# top.net
KiCad netlist of a schematic drawn in Altium Designer
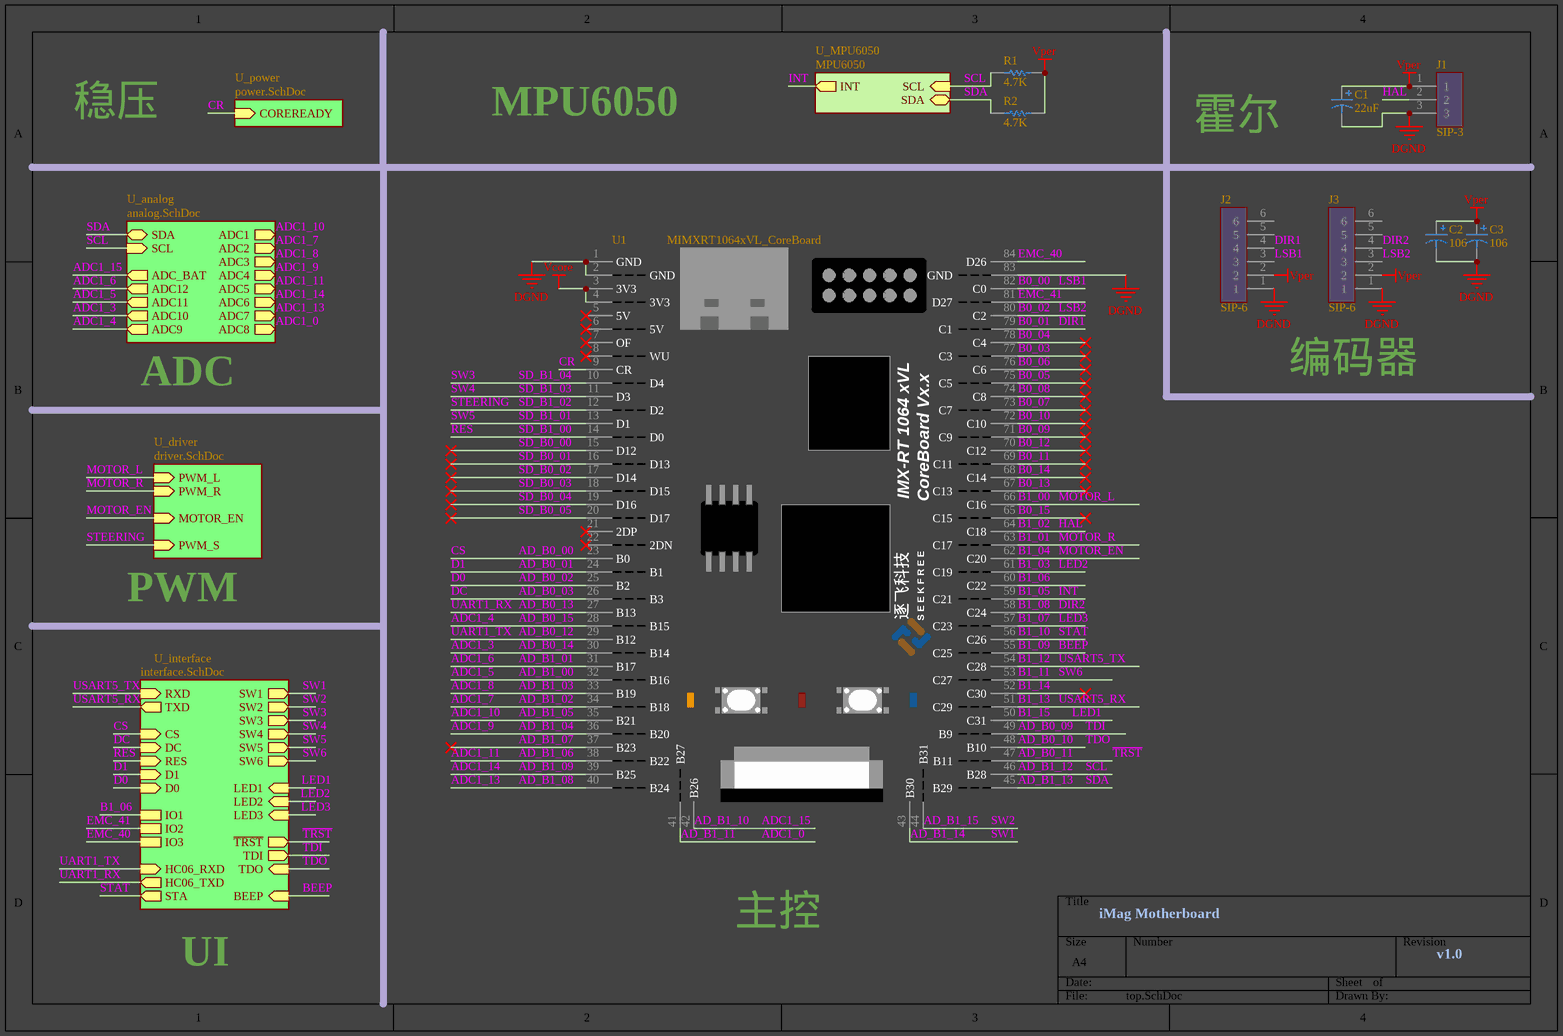
[diagram p0: top.SchDoc]

(export (version "E")
  (design (tool "Eeschema 10.0.6"))
  (components
    (comp (ref "C1")
      (value "22uF")
      (footprint "贴片电解 4*5.4")
      (description "Polarized Capacitor (Axial)")
      (fields (field (name "PUBLISHER") "Altium Limited"))
      (libsource (lib "iMag") (part "电解电容"))
    )
    (comp (ref "C2")
      (value "106")
      (footprint "3216-ce")
      (description "Polarized Capacitor (Axial)")
      (fields (field (name "PUBLISHER") "Altium Limited"))
      (libsource (lib "iMag") (part "电解电容"))
    )
    (comp (ref "C3")
      (value "106")
      (footprint "3216-ce")
      (description "Polarized Capacitor (Axial)")
      (fields (field (name "PUBLISHER") "Altium Limited"))
      (libsource (lib "iMag") (part "电解电容"))
    )
    (comp (ref "J1") (value "SIP-3") (footprint "XH2.54-3SMD") (libsource (lib "iMag") (part "SIP-3")))
    (comp (ref "J2") (value "SIP-6") (footprint "2.54简易牛角座6P") (libsource (lib "iMag") (part "SIP-6")))
    (comp (ref "J3") (value "SIP-6") (footprint "2.54简易牛角座6P") (libsource (lib "iMag") (part "SIP-6")))
    (comp (ref "R1")
      (value "4.7K")
      (footprint "R0402")
      (description "Resistor")
      (fields (field (name "PUBLISHER") "Altium Limited"))
      (libsource (lib "iMag") (part "电阻"))
    )
    (comp (ref "R2")
      (value "4.7K")
      (footprint "R0402")
      (description "Resistor")
      (fields (field (name "PUBLISHER") "Altium Limited"))
      (libsource (lib "iMag") (part "电阻"))
    )
    (comp (ref "U1")
      (value "MIMXRT1064xVL_CoreBoard")
      (footprint "MIMXRT1064xVL_CoreBoard")
      (description "逐飞科技i.MX RT1064核心板整体原理，可直接使用")
      (libsource (lib "iMag") (part "MIMXRT1064xVL_CoreBoard"))
    )
  )
  (nets
    (net (code "1") (name "/ADC1_0") (class "Default")
      (node (ref "U1") (pin "41") (pinfunction "B27_41") (pintype "passive"))
    )
    (net (code "2") (name "/ADC1_3") (class "Default")
      (node (ref "U1") (pin "30") (pinfunction "B14_30") (pintype "passive"))
    )
    (net (code "3") (name "/ADC1_4") (class "Default")
      (node (ref "U1") (pin "28") (pinfunction "B15_28") (pintype "passive"))
    )
    (net (code "4") (name "/ADC1_5") (class "Default")
      (node (ref "U1") (pin "32") (pinfunction "B16_32") (pintype "passive"))
    )
    (net (code "5") (name "/ADC1_6") (class "Default")
      (node (ref "U1") (pin "31") (pinfunction "B17_31") (pintype "passive"))
    )
    (net (code "6") (name "/ADC1_7") (class "Default")
      (node (ref "U1") (pin "34") (pinfunction "B18_34") (pintype "passive"))
    )
    (net (code "7") (name "/ADC1_8") (class "Default")
      (node (ref "U1") (pin "33") (pinfunction "B19_33") (pintype "passive"))
    )
    (net (code "8") (name "/ADC1_9") (class "Default")
      (node (ref "U1") (pin "36") (pinfunction "B20_36") (pintype "passive"))
    )
    (net (code "9") (name "/ADC1_10") (class "Default")
      (node (ref "U1") (pin "35") (pinfunction "B21_35") (pintype "passive"))
    )
    (net (code "10") (name "/ADC1_11") (class "Default")
      (node (ref "U1") (pin "38") (pinfunction "B22_38") (pintype "passive"))
    )
    (net (code "11") (name "/ADC1_13") (class "Default")
      (node (ref "U1") (pin "40") (pinfunction "B24_40") (pintype "passive"))
    )
    (net (code "12") (name "/ADC1_14") (class "Default")
      (node (ref "U1") (pin "39") (pinfunction "B25_39") (pintype "passive"))
    )
    (net (code "13") (name "/ADC1_15") (class "Default")
      (node (ref "U1") (pin "42") (pinfunction "B26_42") (pintype "passive"))
    )
    (net (code "14") (name "/AD_B0_00") (class "Default")
      (node (ref "U1") (pin "23") (pinfunction "B0_23") (pintype "passive"))
    )
    (net (code "15") (name "/AD_B0_01") (class "Default")
      (node (ref "U1") (pin "24") (pinfunction "B1_24") (pintype "passive"))
    )
    (net (code "16") (name "/AD_B0_02") (class "Default")
      (node (ref "U1") (pin "25") (pinfunction "B2_25") (pintype "passive"))
    )
    (net (code "17") (name "/AD_B0_03") (class "Default")
      (node (ref "U1") (pin "26") (pinfunction "B3_26") (pintype "passive"))
    )
    (net (code "18") (name "/AD_B0_09") (class "Default")
      (node (ref "U1") (pin "49") (pinfunction "B9_49") (pintype "passive"))
    )
    (net (code "19") (name "/AD_B0_10") (class "Default")
      (node (ref "U1") (pin "48") (pinfunction "B10_48") (pintype "passive"))
    )
    (net (code "20") (name "/AD_B0_11") (class "Default")
      (node (ref "U1") (pin "47") (pinfunction "B11_47") (pintype "passive"))
    )
    (net (code "21") (name "/AD_B0_12") (class "Default")
      (node (ref "U1") (pin "29") (pinfunction "B12_29") (pintype "passive"))
    )
    (net (code "22") (name "/AD_B0_13") (class "Default")
      (node (ref "U1") (pin "27") (pinfunction "B13_27") (pintype "passive"))
    )
    (net (code "23") (name "/AD_B1_07") (class "Default")
      (node (ref "U1") (pin "37") (pinfunction "B23_37") (pintype "passive+no_connect"))
    )
    (net (code "24") (name "/AD_B1_12") (class "Default")
      (node (ref "R1") (pin "2") (pinfunction "2_2") (pintype "passive"))
      (node (ref "U1") (pin "46") (pinfunction "B28_46") (pintype "passive"))
    )
    (net (code "25") (name "/AD_B1_13") (class "Default")
      (node (ref "R2") (pin "2") (pinfunction "2_2") (pintype "passive"))
      (node (ref "U1") (pin "45") (pinfunction "B29_45") (pintype "passive"))
    )
    (net (code "26") (name "/AD_B1_14") (class "Default")
      (node (ref "U1") (pin "43") (pinfunction "B30_43") (pintype "passive"))
    )
    (net (code "27") (name "/AD_B1_15") (class "Default")
      (node (ref "U1") (pin "44") (pinfunction "B31_44") (pintype "passive"))
    )
    (net (code "28") (name "/B0_00") (class "Default")
      (node (ref "J2") (pin "3") (pinfunction "3_3") (pintype "passive"))
      (node (ref "U1") (pin "82") (pinfunction "C0_82") (pintype "passive"))
    )
    (net (code "29") (name "/B0_01") (class "Default")
      (node (ref "J2") (pin "4") (pinfunction "4_4") (pintype "passive"))
      (node (ref "U1") (pin "79") (pinfunction "C1_79") (pintype "passive"))
    )
    (net (code "30") (name "/B0_02") (class "Default")
      (node (ref "J3") (pin "3") (pinfunction "3_3") (pintype "passive"))
      (node (ref "U1") (pin "80") (pinfunction "C2_80") (pintype "passive"))
    )
    (net (code "31") (name "/B0_03") (class "Default")
      (node (ref "U1") (pin "77") (pinfunction "C3_77") (pintype "passive+no_connect"))
    )
    (net (code "32") (name "/B0_04") (class "Default")
      (node (ref "U1") (pin "78") (pinfunction "C4_78") (pintype "passive+no_connect"))
    )
    (net (code "33") (name "/B0_05") (class "Default")
      (node (ref "U1") (pin "75") (pinfunction "C5_75") (pintype "passive+no_connect"))
    )
    (net (code "34") (name "/B0_06") (class "Default")
      (node (ref "U1") (pin "76") (pinfunction "C6_76") (pintype "passive+no_connect"))
    )
    (net (code "35") (name "/B0_07") (class "Default")
      (node (ref "U1") (pin "73") (pinfunction "C7_73") (pintype "passive+no_connect"))
    )
    (net (code "36") (name "/B0_08") (class "Default")
      (node (ref "U1") (pin "74") (pinfunction "C8_74") (pintype "passive+no_connect"))
    )
    (net (code "37") (name "/B0_09") (class "Default")
      (node (ref "U1") (pin "71") (pinfunction "C9_71") (pintype "passive+no_connect"))
    )
    (net (code "38") (name "/B0_10") (class "Default")
      (node (ref "U1") (pin "72") (pinfunction "C10_72") (pintype "passive+no_connect"))
    )
    (net (code "39") (name "/B0_11") (class "Default")
      (node (ref "U1") (pin "69") (pinfunction "C11_69") (pintype "passive+no_connect"))
    )
    (net (code "40") (name "/B0_12") (class "Default")
      (node (ref "U1") (pin "70") (pinfunction "C12_70") (pintype "passive+no_connect"))
    )
    (net (code "41") (name "/B0_13") (class "Default")
      (node (ref "U1") (pin "67") (pinfunction "C13_67") (pintype "passive+no_connect"))
    )
    (net (code "42") (name "/B0_14") (class "Default")
      (node (ref "U1") (pin "68") (pinfunction "C14_68") (pintype "passive+no_connect"))
    )
    (net (code "43") (name "/B0_15") (class "Default")
      (node (ref "U1") (pin "65") (pinfunction "C15_65") (pintype "passive+no_connect"))
    )
    (net (code "44") (name "/B1_00") (class "Default")
      (node (ref "U1") (pin "66") (pinfunction "C16_66") (pintype "passive"))
    )
    (net (code "45") (name "/B1_01") (class "Default")
      (node (ref "U1") (pin "63") (pinfunction "C17_63") (pintype "passive"))
    )
    (net (code "46") (name "/B1_02") (class "Default")
      (node (ref "J1") (pin "2") (pinfunction "2_2") (pintype "passive"))
      (node (ref "U1") (pin "64") (pinfunction "C18_64") (pintype "passive"))
    )
    (net (code "47") (name "/B1_03") (class "Default")
      (node (ref "U1") (pin "61") (pinfunction "C19_61") (pintype "passive"))
    )
    (net (code "48") (name "/B1_04") (class "Default")
      (node (ref "U1") (pin "62") (pinfunction "C20_62") (pintype "passive"))
    )
    (net (code "49") (name "/B1_05") (class "Default")
      (node (ref "U1") (pin "59") (pinfunction "C21_59") (pintype "passive"))
    )
    (net (code "50") (name "/B1_06") (class "Default")
      (node (ref "U1") (pin "60") (pinfunction "C22_60") (pintype "passive"))
    )
    (net (code "51") (name "/B1_07") (class "Default")
      (node (ref "U1") (pin "57") (pinfunction "C23_57") (pintype "passive"))
    )
    (net (code "52") (name "/B1_08") (class "Default")
      (node (ref "J3") (pin "4") (pinfunction "4_4") (pintype "passive"))
      (node (ref "U1") (pin "58") (pinfunction "C24_58") (pintype "passive"))
    )
    (net (code "53") (name "/B1_09") (class "Default")
      (node (ref "U1") (pin "55") (pinfunction "C25_55") (pintype "passive"))
    )
    (net (code "54") (name "/B1_10") (class "Default")
      (node (ref "U1") (pin "56") (pinfunction "C26_56") (pintype "passive"))
    )
    (net (code "55") (name "/B1_11") (class "Default")
      (node (ref "U1") (pin "53") (pinfunction "C27_53") (pintype "passive"))
    )
    (net (code "56") (name "/B1_12") (class "Default")
      (node (ref "U1") (pin "54") (pinfunction "C28_54") (pintype "passive"))
    )
    (net (code "57") (name "/B1_13") (class "Default")
      (node (ref "U1") (pin "51") (pinfunction "C29_51") (pintype "passive"))
    )
    (net (code "58") (name "/B1_14") (class "Default")
      (node (ref "U1") (pin "52") (pinfunction "C30_52") (pintype "passive+no_connect"))
    )
    (net (code "59") (name "/B1_15") (class "Default")
      (node (ref "U1") (pin "50") (pinfunction "C31_50") (pintype "passive"))
    )
    (net (code "60") (name "/CR") (class "Default")
      (node (ref "U1") (pin "9") (pinfunction "CR_9") (pintype "passive"))
    )
    (net (code "61") (name "/EMC_40") (class "Default")
      (node (ref "U1") (pin "84") (pinfunction "D26_84") (pintype "passive"))
    )
    (net (code "62") (name "/EMC_41") (class "Default")
      (node (ref "U1") (pin "81") (pinfunction "D27_81") (pintype "passive"))
    )
    (net (code "63") (name "/RES") (class "Default")
      (node (ref "U1") (pin "14") (pinfunction "D0_14") (pintype "passive"))
    )
    (net (code "64") (name "/SD_B0_00") (class "Default")
      (node (ref "U1") (pin "15") (pinfunction "D12_15") (pintype "passive+no_connect"))
    )
    (net (code "65") (name "/SD_B0_01") (class "Default")
      (node (ref "U1") (pin "16") (pinfunction "D13_16") (pintype "passive+no_connect"))
    )
    (net (code "66") (name "/SD_B0_02") (class "Default")
      (node (ref "U1") (pin "17") (pinfunction "D14_17") (pintype "passive+no_connect"))
    )
    (net (code "67") (name "/SD_B0_03") (class "Default")
      (node (ref "U1") (pin "18") (pinfunction "D15_18") (pintype "passive+no_connect"))
    )
    (net (code "68") (name "/SD_B0_04") (class "Default")
      (node (ref "U1") (pin "19") (pinfunction "D16_19") (pintype "passive+no_connect"))
    )
    (net (code "69") (name "/SD_B0_05") (class "Default")
      (node (ref "U1") (pin "20") (pinfunction "D17_20") (pintype "passive+no_connect"))
    )
    (net (code "70") (name "/SD_B1_01") (class "Default")
      (node (ref "U1") (pin "13") (pinfunction "D1_13") (pintype "passive"))
    )
    (net (code "71") (name "/SD_B1_02") (class "Default")
      (node (ref "U1") (pin "12") (pinfunction "D2_12") (pintype "passive"))
    )
    (net (code "72") (name "/SD_B1_03") (class "Default")
      (node (ref "U1") (pin "11") (pinfunction "D3_11") (pintype "passive"))
    )
    (net (code "73") (name "/SD_B1_04") (class "Default")
      (node (ref "U1") (pin "10") (pinfunction "D4_10") (pintype "passive"))
    )
    (net (code "74") (name "DGND") (class "Default")
      (node (ref "C1") (pin "2") (pinfunction "2_2") (pintype "passive"))
      (node (ref "C2") (pin "2") (pinfunction "2_2") (pintype "passive"))
      (node (ref "C3") (pin "2") (pinfunction "2_2") (pintype "passive"))
      (node (ref "J1") (pin "3") (pinfunction "3_3") (pintype "passive"))
      (node (ref "J2") (pin "1") (pinfunction "1_1") (pintype "passive"))
      (node (ref "J3") (pin "1") (pinfunction "1_1") (pintype "passive"))
      (node (ref "U1") (pin "1") (pinfunction "GND_1") (pintype "passive"))
      (node (ref "U1") (pin "2") (pinfunction "GND_2") (pintype "passive"))
      (node (ref "U1") (pin "83") (pinfunction "GND_83") (pintype "passive"))
    )
    (net (code "75") (name "Vcore") (class "Default")
      (node (ref "U1") (pin "3") (pinfunction "3V3_3") (pintype "passive"))
      (node (ref "U1") (pin "4") (pinfunction "3V3_4") (pintype "passive"))
    )
    (net (code "76") (name "Vper") (class "Default")
      (node (ref "C1") (pin "1") (pinfunction "1_1") (pintype "passive"))
      (node (ref "C2") (pin "1") (pinfunction "1_1") (pintype "passive"))
      (node (ref "C3") (pin "1") (pinfunction "1_1") (pintype "passive"))
      (node (ref "J1") (pin "1") (pinfunction "1_1") (pintype "passive"))
      (node (ref "J2") (pin "2") (pinfunction "2_2") (pintype "passive"))
      (node (ref "J3") (pin "2") (pinfunction "2_2") (pintype "passive"))
      (node (ref "R1") (pin "1") (pinfunction "1_1") (pintype "passive"))
      (node (ref "R2") (pin "1") (pinfunction "1_1") (pintype "passive"))
    )
    (net (code "77") (name "unconnected-(J2-Pad5)") (class "Default")
      (node (ref "J2") (pin "5") (pinfunction "5_5") (pintype "passive"))
    )
    (net (code "78") (name "unconnected-(J2-Pad6)") (class "Default")
      (node (ref "J2") (pin "6") (pinfunction "6_6") (pintype "passive"))
    )
    (net (code "79") (name "unconnected-(J3-Pad5)") (class "Default")
      (node (ref "J3") (pin "5") (pinfunction "5_5") (pintype "passive"))
    )
    (net (code "80") (name "unconnected-(J3-Pad6)") (class "Default")
      (node (ref "J3") (pin "6") (pinfunction "6_6") (pintype "passive"))
    )
    (net (code "81") (name "unconnected-(U1-2DN-Pad22)") (class "Default")
      (node (ref "U1") (pin "22") (pinfunction "2DN_22") (pintype "passive+no_connect"))
    )
    (net (code "82") (name "unconnected-(U1-2DP-Pad21)") (class "Default")
      (node (ref "U1") (pin "21") (pinfunction "2DP_21") (pintype "passive+no_connect"))
    )
    (net (code "83") (name "unconnected-(U1-5V-Pad5)") (class "Default")
      (node (ref "U1") (pin "5") (pinfunction "5V_5") (pintype "passive+no_connect"))
    )
    (net (code "84") (name "unconnected-(U1-5V-Pad6)") (class "Default")
      (node (ref "U1") (pin "6") (pinfunction "5V_6") (pintype "passive+no_connect"))
    )
    (net (code "85") (name "unconnected-(U1-OF-Pad7)") (class "Default")
      (node (ref "U1") (pin "7") (pinfunction "OF_7") (pintype "passive+no_connect"))
    )
    (net (code "86") (name "unconnected-(U1-WU-Pad8)") (class "Default")
      (node (ref "U1") (pin "8") (pinfunction "WU_8") (pintype "passive+no_connect"))
    )
  )
)
